# v1_3.net
KiCad netlist of a schematic drawn in EAGLE
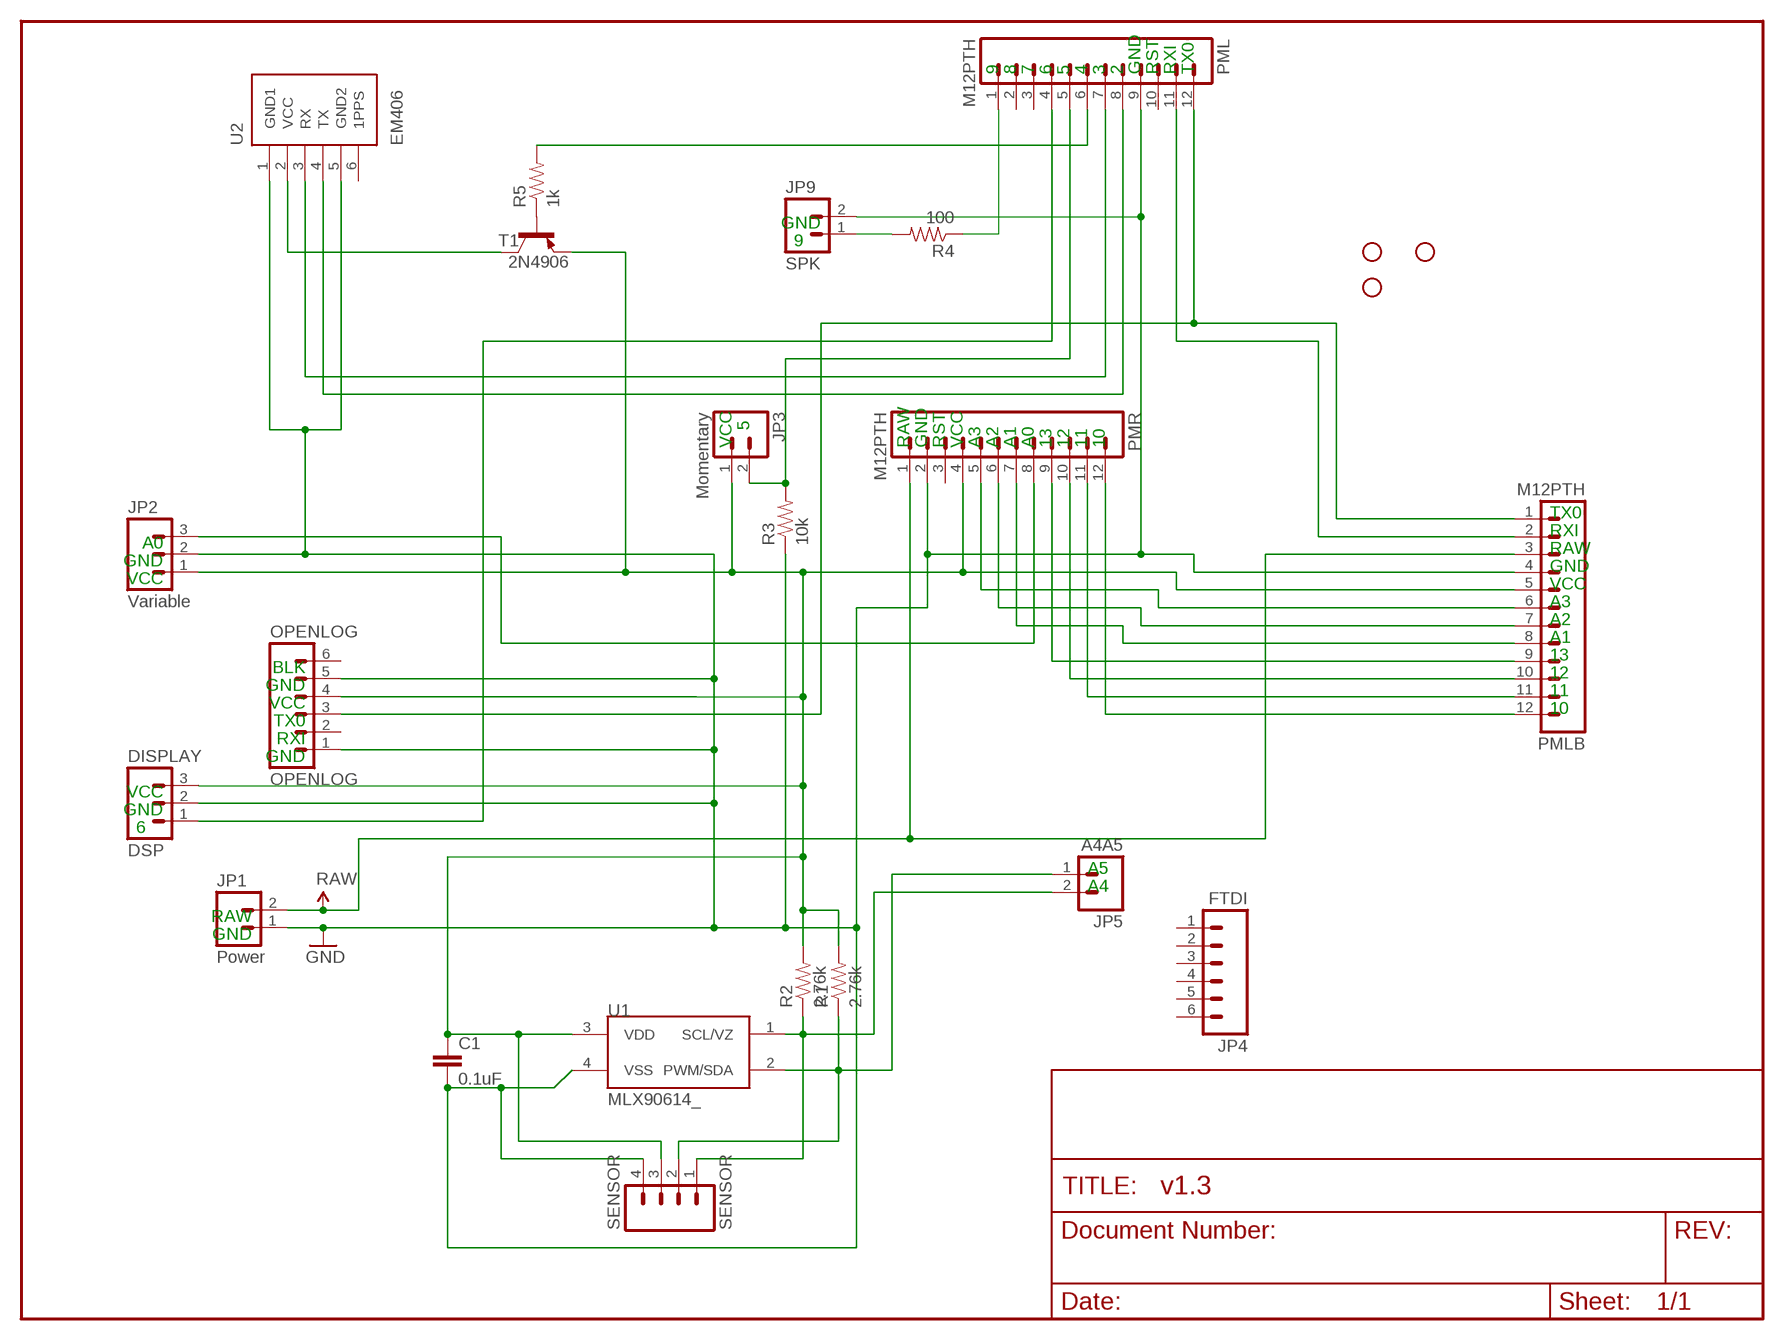
[diagram p0: schematic, sheet 1]

(export (version "E")
  (design (tool "Eeschema 10.0.6"))
  (components
    (comp (ref "2N4906")
      (value "T1")
      (footprint "eagle-import:TO92-EBC")
      (libsource (lib "eagle-import") (part "-PNP-TO92-EBC2N3906"))
    )
    (comp (ref "C1")
      (value "0.1uF")
      (footprint "eagle-import:CAP-PTH-LARGE")
      (libsource (lib "eagle-import") (part "CAPPTH3"))
    )
    (comp (ref "DISPLAY")
      (value "DSP")
      (footprint "eagle-import:SCREWTERMINAL-3.5MM-3_LOCK.007S")
      (libsource (lib "eagle-import") (part "M03SCREW_LOCK"))
    )
    (comp (ref "JP1")
      (value "Power")
      (footprint "eagle-import:JST-2-PTH")
      (libsource (lib "eagle-import") (part "M02JST-PTH-2"))
    )
    (comp (ref "JP2")
      (value "Variable")
      (footprint "eagle-import:SCREWTERMINAL-3.5MM-3_LOCK.007S")
      (libsource (lib "eagle-import") (part "M03SCREW_LOCK"))
    )
    (comp (ref "JP3")
      (value "Momentary")
      (footprint "eagle-import:JST-2-PTH")
      (libsource (lib "eagle-import") (part "M02JST-PTH-2"))
    )
    (comp (ref "JP4")
      (value "FTDI")
      (footprint "eagle-import:1X06")
      (libsource (lib "eagle-import") (part "M06SIP"))
    )
    (comp (ref "JP5")
      (value "A4A5")
      (footprint "eagle-import:1X02")
      (libsource (lib "eagle-import") (part "M02PTH"))
    )
    (comp (ref "JP6")
      (value "STAND-OFFTIGHT")
      (footprint "eagle-import:STAND-OFF-TIGHT")
      (libsource (lib "eagle-import") (part "STAND-OFFTIGHT"))
    )
    (comp (ref "JP7")
      (value "STAND-OFFTIGHT")
      (footprint "eagle-import:STAND-OFF-TIGHT")
      (libsource (lib "eagle-import") (part "STAND-OFFTIGHT"))
    )
    (comp (ref "JP8")
      (value "STAND-OFFTIGHT")
      (footprint "eagle-import:STAND-OFF-TIGHT")
      (libsource (lib "eagle-import") (part "STAND-OFFTIGHT"))
    )
    (comp (ref "JP9")
      (value "SPK")
      (footprint "eagle-import:SCREWTERMINAL-3.5MM-2")
      (libsource (lib "eagle-import") (part "M023.5MM"))
    )
    (comp (ref "OPENLOG")
      (value "OPENLOG")
      (footprint "eagle-import:1X06_LOCK")
      (libsource (lib "eagle-import") (part "M06LOCK"))
    )
    (comp (ref "PML")
      (value "M12PTH")
      (footprint "eagle-import:1X12")
      (libsource (lib "eagle-import") (part "M12PTH"))
    )
    (comp (ref "PMLB")
      (value "M12PTH")
      (footprint "eagle-import:1X12")
      (libsource (lib "eagle-import") (part "M12PTH"))
    )
    (comp (ref "PMR")
      (value "M12PTH")
      (footprint "eagle-import:1X12")
      (libsource (lib "eagle-import") (part "M12PTH"))
    )
    (comp (ref "R1")
      (value "2.76k")
      (footprint "eagle-import:AXIAL-0.4")
      (libsource (lib "eagle-import") (part "RESISTORPTH-1/4W"))
    )
    (comp (ref "R2")
      (value "2.76k")
      (footprint "eagle-import:AXIAL-0.4")
      (libsource (lib "eagle-import") (part "RESISTORPTH-1/4W"))
    )
    (comp (ref "R3")
      (value "10k")
      (footprint "eagle-import:AXIAL-0.4")
      (libsource (lib "eagle-import") (part "RESISTORPTH-1/4W"))
    )
    (comp (ref "R4")
      (value "100")
      (footprint "eagle-import:AXIAL-0.4")
      (libsource (lib "eagle-import") (part "RESISTORPTH-1/4W"))
    )
    (comp (ref "R5")
      (value "1k")
      (footprint "eagle-import:AXIAL-0.4")
      (libsource (lib "eagle-import") (part "RESISTORPTH-1/4W"))
    )
    (comp (ref "SENSOR")
      (value "SENSOR")
      (footprint "eagle-import:SCREWTERMINAL-3.5MM-4_LOCK")
      (libsource (lib "eagle-import") (part "M04SCREW_LOCK"))
    )
    (comp (ref "U1")
      (value "MLX90614_")
      (footprint "eagle-import:TO-39")
      (libsource (lib "eagle-import") (part "MLX90614_"))
    )
    (comp (ref "U2")
      (value "EM406")
      (footprint "eagle-import:EM406")
      (libsource (lib "eagle-import") (part "EM406"))
    )
  )
  (nets
    (net (code "1") (name "GND") (class "Default")
      (node (ref "C1") (pin "2") (pinfunction "2_2") (pintype "passive"))
      (node (ref "DISPLAY") (pin "2") (pinfunction "2_2") (pintype "passive"))
      (node (ref "JP1") (pin "1") (pinfunction "1_1") (pintype "passive"))
      (node (ref "JP2") (pin "2") (pinfunction "2_2") (pintype "passive"))
      (node (ref "JP9") (pin "2") (pinfunction "2_2") (pintype "passive"))
      (node (ref "OPENLOG") (pin "1") (pinfunction "1_1") (pintype "passive"))
      (node (ref "OPENLOG") (pin "5") (pinfunction "5_5") (pintype "passive"))
      (node (ref "PML") (pin "9") (pinfunction "9_9") (pintype "passive"))
      (node (ref "PMLB") (pin "4") (pinfunction "4_4") (pintype "passive"))
      (node (ref "PMR") (pin "2") (pinfunction "2_2") (pintype "passive"))
      (node (ref "R3") (pin "P$1") (pinfunction "1_P$1") (pintype "passive"))
      (node (ref "SENSOR") (pin "4") (pinfunction "4_4") (pintype "passive"))
      (node (ref "U1") (pin "4") (pinfunction "VSS_4") (pintype "bidirectional"))
      (node (ref "U2") (pin "1") (pinfunction "GND1_1") (pintype "bidirectional"))
      (node (ref "U2") (pin "5") (pinfunction "GND2_5") (pintype "bidirectional"))
    )
    (net (code "2") (name "Net-(DISPLAY-Pad1)") (class "Default")
      (node (ref "DISPLAY") (pin "1") (pinfunction "1_1") (pintype "passive"))
      (node (ref "PML") (pin "4") (pinfunction "4_4") (pintype "passive"))
    )
    (net (code "3") (name "Net-(JP2-Pad3)") (class "Default")
      (node (ref "JP2") (pin "3") (pinfunction "3_3") (pintype "passive"))
      (node (ref "PMR") (pin "8") (pinfunction "8_8") (pintype "passive"))
    )
    (net (code "4") (name "Net-(OPENLOG-Pad3)") (class "Default")
      (node (ref "OPENLOG") (pin "3") (pinfunction "3_3") (pintype "passive"))
      (node (ref "PML") (pin "12") (pinfunction "12_12") (pintype "passive"))
      (node (ref "PMLB") (pin "1") (pinfunction "1_1") (pintype "passive"))
    )
    (net (code "5") (name "Net-(PML-Pad11)") (class "Default")
      (node (ref "PML") (pin "11") (pinfunction "11_11") (pintype "passive"))
      (node (ref "PMLB") (pin "2") (pinfunction "2_2") (pintype "passive"))
    )
    (net (code "6") (name "Net-(PMLB-Pad6)") (class "Default")
      (node (ref "PMLB") (pin "6") (pinfunction "6_6") (pintype "passive"))
      (node (ref "PMR") (pin "5") (pinfunction "5_5") (pintype "passive"))
    )
    (net (code "7") (name "Net-(PMLB-Pad7)") (class "Default")
      (node (ref "PMLB") (pin "7") (pinfunction "7_7") (pintype "passive"))
      (node (ref "PMR") (pin "6") (pinfunction "6_6") (pintype "passive"))
    )
    (net (code "8") (name "Net-(PMLB-Pad8)") (class "Default")
      (node (ref "PMLB") (pin "8") (pinfunction "8_8") (pintype "passive"))
      (node (ref "PMR") (pin "7") (pinfunction "7_7") (pintype "passive"))
    )
    (net (code "9") (name "Net-(PMLB-Pad9)") (class "Default")
      (node (ref "PMLB") (pin "9") (pinfunction "9_9") (pintype "passive"))
      (node (ref "PMR") (pin "9") (pinfunction "9_9") (pintype "passive"))
    )
    (net (code "10") (name "Net-(PMLB-Pad10)") (class "Default")
      (node (ref "PMLB") (pin "10") (pinfunction "10_10") (pintype "passive"))
      (node (ref "PMR") (pin "10") (pinfunction "10_10") (pintype "passive"))
    )
    (net (code "11") (name "Net-(PMLB-Pad11)") (class "Default")
      (node (ref "PMLB") (pin "11") (pinfunction "11_11") (pintype "passive"))
      (node (ref "PMR") (pin "11") (pinfunction "11_11") (pintype "passive"))
    )
    (net (code "12") (name "Net-(PMLB-Pad12)") (class "Default")
      (node (ref "PMLB") (pin "12") (pinfunction "12_12") (pintype "passive"))
      (node (ref "PMR") (pin "12") (pinfunction "12_12") (pintype "passive"))
    )
    (net (code "13") (name "Net-(R1-1)") (class "Default")
      (node (ref "JP5") (pin "1") (pinfunction "1_1") (pintype "passive"))
      (node (ref "R1") (pin "P$1") (pinfunction "1_P$1") (pintype "passive"))
      (node (ref "SENSOR") (pin "2") (pinfunction "2_2") (pintype "passive"))
      (node (ref "U1") (pin "2") (pinfunction "PWM/SDA_2") (pintype "bidirectional"))
    )
    (net (code "14") (name "Net-(R1-2)") (class "Default")
      (node (ref "2N4906") (pin "E") (pinfunction "E_E") (pintype "passive"))
      (node (ref "C1") (pin "1") (pinfunction "1_1") (pintype "passive"))
      (node (ref "DISPLAY") (pin "3") (pinfunction "3_3") (pintype "passive"))
      (node (ref "JP2") (pin "1") (pinfunction "1_1") (pintype "passive"))
      (node (ref "JP3") (pin "1") (pinfunction "1_1") (pintype "passive"))
      (node (ref "OPENLOG") (pin "4") (pinfunction "4_4") (pintype "passive"))
      (node (ref "PMLB") (pin "5") (pinfunction "5_5") (pintype "passive"))
      (node (ref "PMR") (pin "4") (pinfunction "4_4") (pintype "passive"))
      (node (ref "R1") (pin "P$2") (pinfunction "2_P$2") (pintype "passive"))
      (node (ref "R2") (pin "P$2") (pinfunction "2_P$2") (pintype "passive"))
      (node (ref "SENSOR") (pin "3") (pinfunction "3_3") (pintype "passive"))
      (node (ref "U1") (pin "3") (pinfunction "VDD_3") (pintype "bidirectional"))
    )
    (net (code "15") (name "Net-(R2-1)") (class "Default")
      (node (ref "JP5") (pin "2") (pinfunction "2_2") (pintype "passive"))
      (node (ref "R2") (pin "P$1") (pinfunction "1_P$1") (pintype "passive"))
      (node (ref "SENSOR") (pin "1") (pinfunction "1_1") (pintype "passive"))
      (node (ref "U1") (pin "1") (pinfunction "SCL/VZ_1") (pintype "bidirectional"))
    )
    (net (code "16") (name "Net-(R3-2)") (class "Default")
      (node (ref "JP3") (pin "2") (pinfunction "2_2") (pintype "passive"))
      (node (ref "PML") (pin "5") (pinfunction "5_5") (pintype "passive"))
      (node (ref "R3") (pin "P$2") (pinfunction "2_P$2") (pintype "passive"))
    )
    (net (code "17") (name "Net-(R4-1)") (class "Default")
      (node (ref "PML") (pin "1") (pinfunction "1_1") (pintype "passive"))
      (node (ref "R4") (pin "P$1") (pinfunction "1_P$1") (pintype "passive"))
    )
    (net (code "18") (name "Net-(R4-2)") (class "Default")
      (node (ref "JP9") (pin "1") (pinfunction "1_1") (pintype "passive"))
      (node (ref "R4") (pin "P$2") (pinfunction "2_P$2") (pintype "passive"))
    )
    (net (code "19") (name "Net-(R5-1)") (class "Default")
      (node (ref "2N4906") (pin "B") (pinfunction "B_B") (pintype "passive"))
      (node (ref "R5") (pin "P$1") (pinfunction "1_P$1") (pintype "passive"))
    )
    (net (code "20") (name "Net-(R5-2)") (class "Default")
      (node (ref "PML") (pin "6") (pinfunction "6_6") (pintype "passive"))
      (node (ref "R5") (pin "P$2") (pinfunction "2_P$2") (pintype "passive"))
    )
    (net (code "21") (name "Net-(U2-RX)") (class "Default")
      (node (ref "PML") (pin "7") (pinfunction "7_7") (pintype "passive"))
      (node (ref "U2") (pin "3") (pinfunction "RX_3") (pintype "bidirectional"))
    )
    (net (code "22") (name "Net-(U2-TX)") (class "Default")
      (node (ref "PML") (pin "8") (pinfunction "8_8") (pintype "passive"))
      (node (ref "U2") (pin "4") (pinfunction "TX_4") (pintype "bidirectional"))
    )
    (net (code "23") (name "Net-(U2-VCC)") (class "Default")
      (node (ref "2N4906") (pin "C") (pinfunction "C_C") (pintype "passive"))
      (node (ref "U2") (pin "2") (pinfunction "VCC_2") (pintype "bidirectional"))
    )
    (net (code "24") (name "RAW") (class "Default")
      (node (ref "JP1") (pin "2") (pinfunction "2_2") (pintype "passive"))
      (node (ref "PMLB") (pin "3") (pinfunction "3_3") (pintype "passive"))
      (node (ref "PMR") (pin "1") (pinfunction "1_1") (pintype "passive"))
    )
    (net (code "25") (name "unconnected-(JP4-Pad1)") (class "Default")
      (node (ref "JP4") (pin "1") (pinfunction "1_1") (pintype "passive"))
    )
    (net (code "26") (name "unconnected-(JP4-Pad2)") (class "Default")
      (node (ref "JP4") (pin "2") (pinfunction "2_2") (pintype "passive"))
    )
    (net (code "27") (name "unconnected-(JP4-Pad3)") (class "Default")
      (node (ref "JP4") (pin "3") (pinfunction "3_3") (pintype "passive"))
    )
    (net (code "28") (name "unconnected-(JP4-Pad4)") (class "Default")
      (node (ref "JP4") (pin "4") (pinfunction "4_4") (pintype "passive"))
    )
    (net (code "29") (name "unconnected-(JP4-Pad5)") (class "Default")
      (node (ref "JP4") (pin "5") (pinfunction "5_5") (pintype "passive"))
    )
    (net (code "30") (name "unconnected-(JP4-Pad6)") (class "Default")
      (node (ref "JP4") (pin "6") (pinfunction "6_6") (pintype "passive"))
    )
    (net (code "31") (name "unconnected-(OPENLOG-Pad2)") (class "Default")
      (node (ref "OPENLOG") (pin "2") (pinfunction "2_2") (pintype "passive"))
    )
    (net (code "32") (name "unconnected-(OPENLOG-Pad6)") (class "Default")
      (node (ref "OPENLOG") (pin "6") (pinfunction "6_6") (pintype "passive"))
    )
    (net (code "33") (name "unconnected-(PML-Pad2)") (class "Default")
      (node (ref "PML") (pin "2") (pinfunction "2_2") (pintype "passive"))
    )
    (net (code "34") (name "unconnected-(PML-Pad3)") (class "Default")
      (node (ref "PML") (pin "3") (pinfunction "3_3") (pintype "passive"))
    )
    (net (code "35") (name "unconnected-(PML-Pad10)") (class "Default")
      (node (ref "PML") (pin "10") (pinfunction "10_10") (pintype "passive"))
    )
    (net (code "36") (name "unconnected-(PMR-Pad3)") (class "Default")
      (node (ref "PMR") (pin "3") (pinfunction "3_3") (pintype "passive"))
    )
    (net (code "37") (name "unconnected-(U2-1PPS-Pad6)") (class "Default")
      (node (ref "U2") (pin "6") (pinfunction "1PPS_6") (pintype "bidirectional"))
    )
  )
)
